# axiom_beta_plugin_module_1xHDMI_in_v0_1_.net
KiCad netlist of a schematic drawn in EAGLE
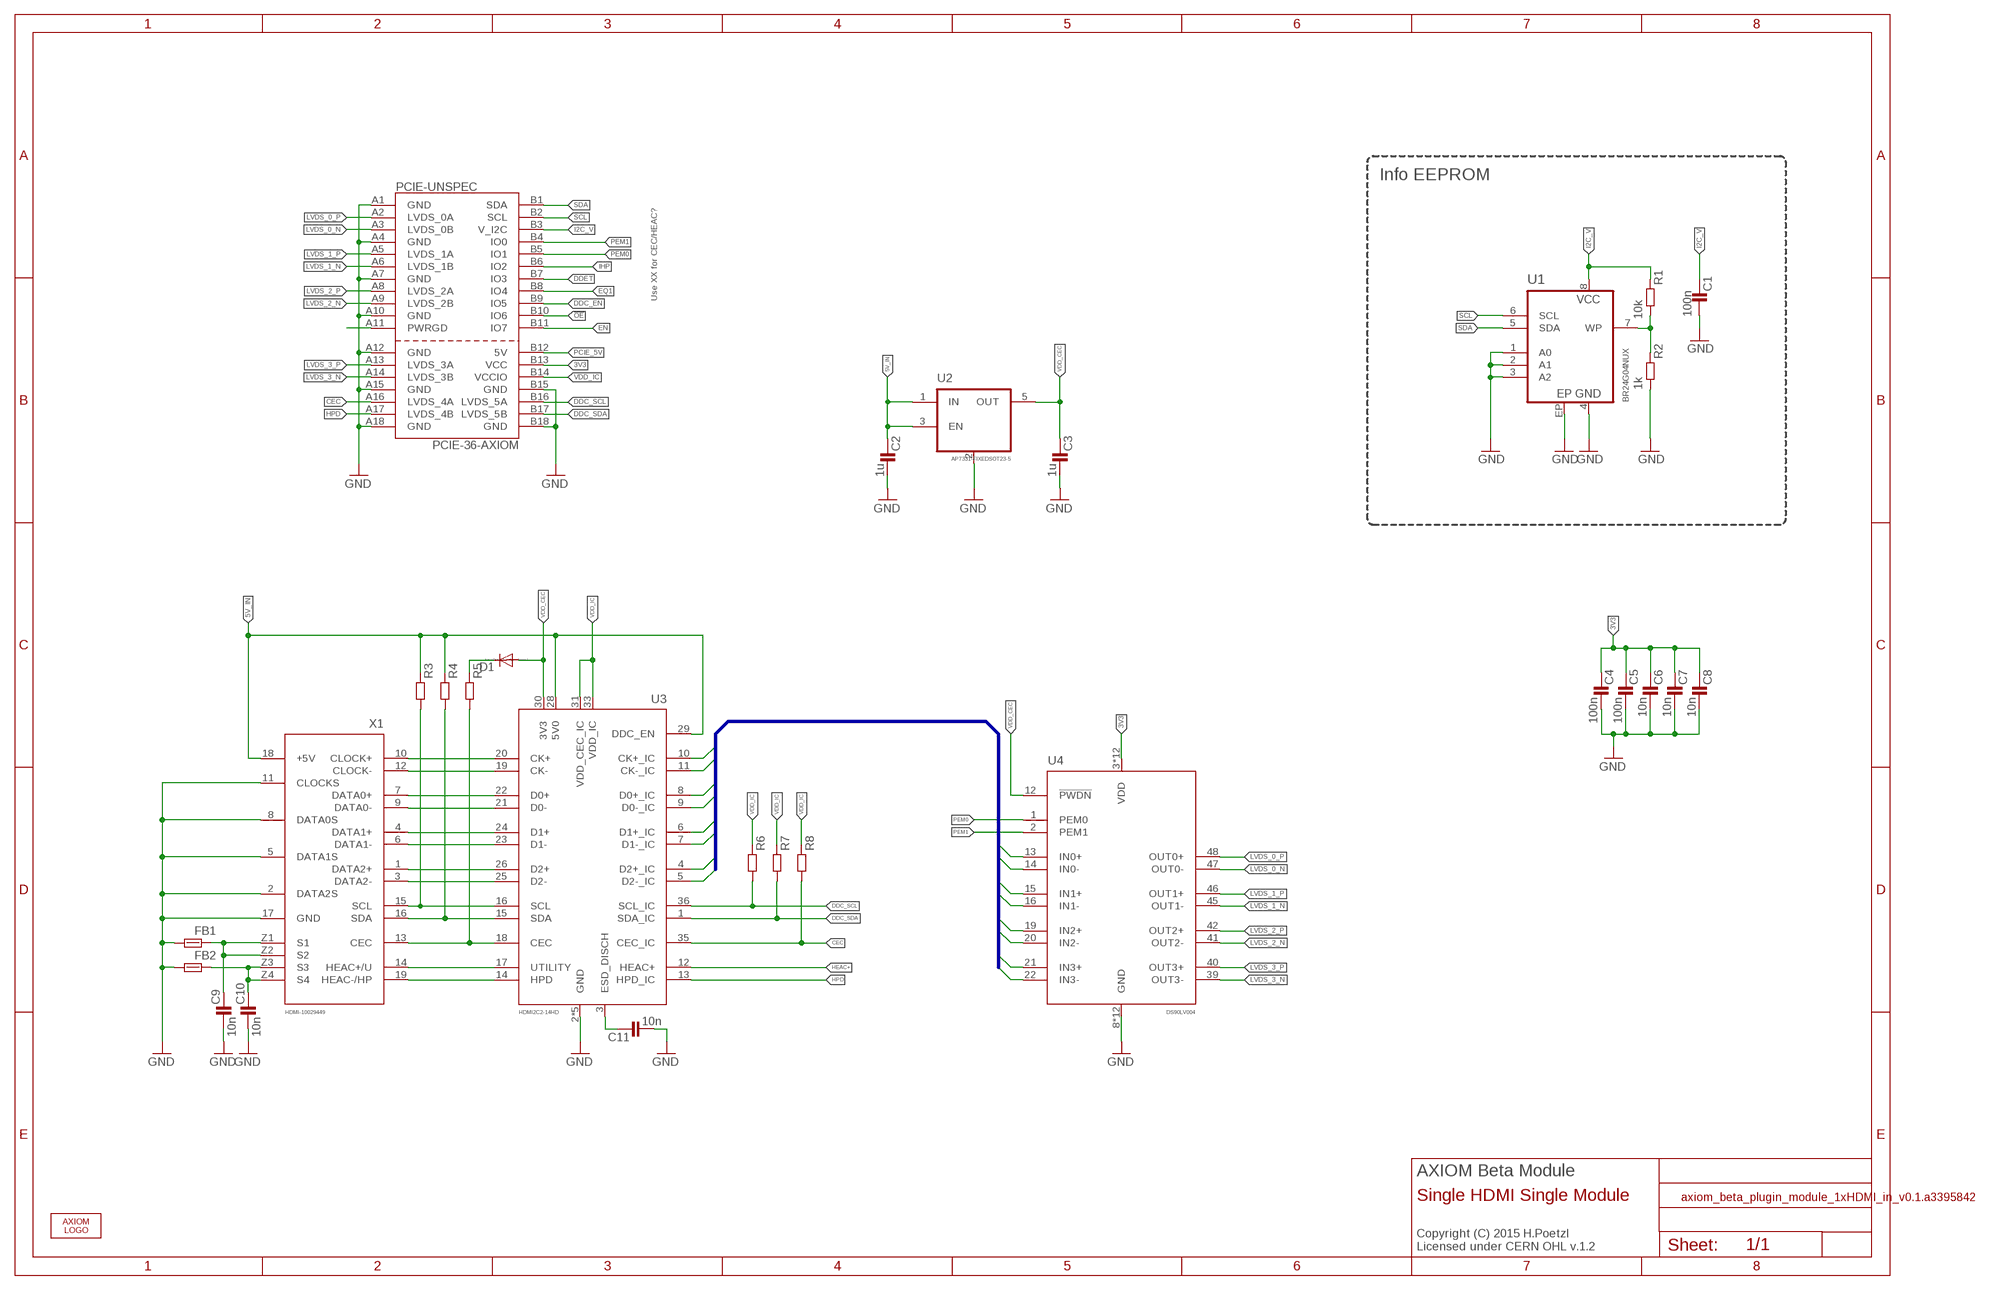
[diagram p0: schematic, sheet 1]

(export (version "E")
  (design (tool "Eeschema 10.0.6"))
  (components
    (comp (ref "C1")
      (value "100n")
      (footprint "eagle-import:0402-B")
      (libsource (lib "eagle-import") (part "C0402-B"))
    )
    (comp (ref "C2")
      (value "1u")
      (footprint "eagle-import:0402-B")
      (libsource (lib "eagle-import") (part "C0402-B"))
    )
    (comp (ref "C3")
      (value "1u")
      (footprint "eagle-import:0402-B")
      (libsource (lib "eagle-import") (part "C0402-B"))
    )
    (comp (ref "C4")
      (value "100n")
      (footprint "eagle-import:0402-B")
      (libsource (lib "eagle-import") (part "C0402-B"))
    )
    (comp (ref "C5")
      (value "100n")
      (footprint "eagle-import:0402-B")
      (libsource (lib "eagle-import") (part "C0402-B"))
    )
    (comp (ref "C6")
      (value "10n")
      (footprint "eagle-import:0402-B")
      (libsource (lib "eagle-import") (part "C0402-B"))
    )
    (comp (ref "C7")
      (value "10n")
      (footprint "eagle-import:0402-B")
      (libsource (lib "eagle-import") (part "C0402-B"))
    )
    (comp (ref "C8")
      (value "10n")
      (footprint "eagle-import:0402-B")
      (libsource (lib "eagle-import") (part "C0402-B"))
    )
    (comp (ref "C9")
      (value "10n")
      (footprint "eagle-import:0402-B")
      (libsource (lib "eagle-import") (part "C0402-B"))
    )
    (comp (ref "C10")
      (value "10n")
      (footprint "eagle-import:0402-B")
      (libsource (lib "eagle-import") (part "C0402-B"))
    )
    (comp (ref "C11")
      (value "10n")
      (footprint "eagle-import:0402-B")
      (libsource (lib "eagle-import") (part "C0402-B"))
    )
    (comp (ref "D1")
      (value "DIODE-SOD523")
      (footprint "eagle-import:SOD523")
      (libsource (lib "eagle-import") (part "DIODE-SOD523"))
    )
    (comp (ref "FB1")
      (value "FB0603-B")
      (footprint "eagle-import:0603-B")
      (libsource (lib "eagle-import") (part "FB0603-B"))
    )
    (comp (ref "FB2")
      (value "FB0603-B")
      (footprint "eagle-import:0603-B")
      (libsource (lib "eagle-import") (part "FB0603-B"))
    )
    (comp (ref "PCIE-UNSPEC")
      (value "PCIE-36-AXIOM")
      (footprint "eagle-import:PCIE-36-AXIOM")
      (libsource (lib "eagle-import") (part "PCIE-36-AXIOM"))
    )
    (comp (ref "R1")
      (value "10k")
      (footprint "eagle-import:0402-B")
      (libsource (lib "eagle-import") (part "R0402-B"))
    )
    (comp (ref "R2")
      (value "1k")
      (footprint "eagle-import:0402-B")
      (libsource (lib "eagle-import") (part "R0402-B"))
    )
    (comp (ref "R3")
      (value "R0402-B")
      (footprint "eagle-import:0402-B")
      (libsource (lib "eagle-import") (part "R0402-B"))
    )
    (comp (ref "R4")
      (value "R0402-B")
      (footprint "eagle-import:0402-B")
      (libsource (lib "eagle-import") (part "R0402-B"))
    )
    (comp (ref "R5")
      (value "R0402-B")
      (footprint "eagle-import:0402-B")
      (libsource (lib "eagle-import") (part "R0402-B"))
    )
    (comp (ref "R6")
      (value "R0402-B")
      (footprint "eagle-import:0402-B")
      (libsource (lib "eagle-import") (part "R0402-B"))
    )
    (comp (ref "R7")
      (value "R0402-B")
      (footprint "eagle-import:0402-B")
      (libsource (lib "eagle-import") (part "R0402-B"))
    )
    (comp (ref "R8")
      (value "R0402-B")
      (footprint "eagle-import:0402-B")
      (libsource (lib "eagle-import") (part "R0402-B"))
    )
    (comp (ref "U$")
      (value "AXIOM_LOGO459X70")
      (footprint "eagle-import:AXIOM_LOGO_459X70")
      (libsource (lib "eagle-import") (part "AXIOM_LOGO459X70"))
    )
    (comp (ref "U1")
      (value "BR24G04NUX")
      (footprint "eagle-import:DFN200X300X100-9N")
      (libsource (lib "eagle-import") (part "BR24G04NUX"))
    )
    (comp (ref "U2")
      (value "AP7331-FIXEDSOT23-5")
      (footprint "eagle-import:SOT23-5")
      (libsource (lib "eagle-import") (part "AP7331-FIXEDSOT23-5"))
    )
    (comp (ref "U3")
      (value "HDMI2C2-14HD")
      (footprint "eagle-import:QFN50P650L90W-25N")
      (libsource (lib "eagle-import") (part "HDMI2C2-14HD"))
    )
    (comp (ref "U4")
      (value "DS90LV004")
      (footprint "eagle-import:QFP50P900X900X160-48N")
      (libsource (lib "eagle-import") (part "DS90LV004"))
    )
    (comp (ref "X1")
      (value "HDMI-10029449")
      (footprint "eagle-import:10029449-X01XLF")
      (libsource (lib "eagle-import") (part "HDMI-10029449"))
    )
  )
  (nets
    (net (code "1") (name "/IN0+") (class "Default")
      (node (ref "U3") (pin "4") (pinfunction "D2+_IC_4") (pintype "bidirectional"))
      (node (ref "U4") (pin "13") (pinfunction "IN0+_13") (pintype "bidirectional"))
    )
    (net (code "2") (name "/IN0-") (class "Default")
      (node (ref "U3") (pin "5") (pinfunction "D2-_IC_5") (pintype "bidirectional"))
      (node (ref "U4") (pin "14") (pinfunction "IN0-_14") (pintype "bidirectional"))
    )
    (net (code "3") (name "/IN1+") (class "Default")
      (node (ref "U3") (pin "6") (pinfunction "D1+_IC_6") (pintype "bidirectional"))
      (node (ref "U4") (pin "15") (pinfunction "IN1+_15") (pintype "bidirectional"))
    )
    (net (code "4") (name "/IN1-") (class "Default")
      (node (ref "U3") (pin "7") (pinfunction "D1-_IC_7") (pintype "bidirectional"))
      (node (ref "U4") (pin "16") (pinfunction "IN1-_16") (pintype "bidirectional"))
    )
    (net (code "5") (name "/IN2+") (class "Default")
      (node (ref "U3") (pin "8") (pinfunction "D0+_IC_8") (pintype "bidirectional"))
      (node (ref "U4") (pin "19") (pinfunction "IN2+_19") (pintype "bidirectional"))
    )
    (net (code "6") (name "/IN2-") (class "Default")
      (node (ref "U3") (pin "9") (pinfunction "D0-_IC_9") (pintype "bidirectional"))
      (node (ref "U4") (pin "20") (pinfunction "IN2-_20") (pintype "bidirectional"))
    )
    (net (code "7") (name "/IN3+") (class "Default")
      (node (ref "U3") (pin "10") (pinfunction "CK+_IC_10") (pintype "bidirectional"))
      (node (ref "U4") (pin "21") (pinfunction "IN3+_21") (pintype "bidirectional"))
    )
    (net (code "8") (name "/IN3-") (class "Default")
      (node (ref "U3") (pin "11") (pinfunction "CK-_IC_11") (pintype "bidirectional"))
      (node (ref "U4") (pin "22") (pinfunction "IN3-_22") (pintype "bidirectional"))
    )
    (net (code "9") (name "/~{OE}") (class "Default")
      (node (ref "PCIE-UNSPEC") (pin "B10") (pinfunction "IO6_B10") (pintype "passive"))
    )
    (net (code "10") (name "3V3") (class "Default")
      (node (ref "C4") (pin "1") (pinfunction "1_1") (pintype "passive"))
      (node (ref "C5") (pin "1") (pinfunction "1_1") (pintype "passive"))
      (node (ref "C6") (pin "1") (pinfunction "1_1") (pintype "passive"))
      (node (ref "C7") (pin "1") (pinfunction "1_1") (pintype "passive"))
      (node (ref "C8") (pin "1") (pinfunction "1_1") (pintype "passive"))
      (node (ref "PCIE-UNSPEC") (pin "B13") (pinfunction "VCC_B13") (pintype "passive"))
      (node (ref "U4") (pin "10") (pinfunction "VDD_10") (pintype "power_in"))
      (node (ref "U4") (pin "11") (pinfunction "VDD_11") (pintype "power_in"))
      (node (ref "U4") (pin "27") (pinfunction "VDD_27") (pintype "power_in"))
      (node (ref "U4") (pin "28") (pinfunction "VDD_28") (pintype "power_in"))
      (node (ref "U4") (pin "29") (pinfunction "VDD_29") (pintype "power_in"))
      (node (ref "U4") (pin "3") (pinfunction "VDD_3") (pintype "power_in"))
      (node (ref "U4") (pin "32") (pinfunction "VDD_32") (pintype "power_in"))
      (node (ref "U4") (pin "33") (pinfunction "VDD_33") (pintype "power_in"))
      (node (ref "U4") (pin "34") (pinfunction "VDD_34") (pintype "power_in"))
      (node (ref "U4") (pin "4") (pinfunction "VDD_4") (pintype "power_in"))
      (node (ref "U4") (pin "5") (pinfunction "VDD_5") (pintype "power_in"))
      (node (ref "U4") (pin "7") (pinfunction "VDD_7") (pintype "power_in"))
    )
    (net (code "11") (name "5V_IN") (class "Default")
      (node (ref "C2") (pin "1") (pinfunction "1_1") (pintype "passive"))
      (node (ref "R3") (pin "1") (pinfunction "1_1") (pintype "passive"))
      (node (ref "R4") (pin "1") (pinfunction "1_1") (pintype "passive"))
      (node (ref "U2") (pin "1") (pinfunction "IN_1") (pintype "power_in"))
      (node (ref "U2") (pin "3") (pinfunction "EN_3") (pintype "input"))
      (node (ref "U3") (pin "28") (pinfunction "5V0_28") (pintype "power_in"))
      (node (ref "U3") (pin "29") (pinfunction "DDC_EN_29") (pintype "bidirectional"))
      (node (ref "X1") (pin "18") (pinfunction "+5V_18") (pintype "power_in"))
    )
    (net (code "12") (name "CEC") (class "Default")
      (node (ref "PCIE-UNSPEC") (pin "A16") (pinfunction "LVDS_4A_A16") (pintype "passive"))
      (node (ref "R8") (pin "2") (pinfunction "2_2") (pintype "passive"))
      (node (ref "U3") (pin "35") (pinfunction "CEC_IC_35") (pintype "bidirectional"))
    )
    (net (code "13") (name "DDC_EN") (class "Default")
      (node (ref "PCIE-UNSPEC") (pin "B9") (pinfunction "IO5_B9") (pintype "passive"))
    )
    (net (code "14") (name "DDC_SCL") (class "Default")
      (node (ref "PCIE-UNSPEC") (pin "B16") (pinfunction "LVDS_5A_B16") (pintype "passive"))
      (node (ref "R6") (pin "2") (pinfunction "2_2") (pintype "passive"))
      (node (ref "U3") (pin "36") (pinfunction "SCL_IC_36") (pintype "bidirectional"))
    )
    (net (code "15") (name "DDC_SDA") (class "Default")
      (node (ref "PCIE-UNSPEC") (pin "B17") (pinfunction "LVDS_5B_B17") (pintype "passive"))
      (node (ref "R7") (pin "2") (pinfunction "2_2") (pintype "passive"))
      (node (ref "U3") (pin "1") (pinfunction "SDA_IC_1") (pintype "bidirectional"))
    )
    (net (code "16") (name "DDET") (class "Default")
      (node (ref "PCIE-UNSPEC") (pin "B7") (pinfunction "IO3_B7") (pintype "passive"))
    )
    (net (code "17") (name "EN") (class "Default")
      (node (ref "PCIE-UNSPEC") (pin "B11") (pinfunction "IO7_B11") (pintype "passive"))
    )
    (net (code "18") (name "EQ1") (class "Default")
      (node (ref "PCIE-UNSPEC") (pin "B8") (pinfunction "IO4_B8") (pintype "passive"))
    )
    (net (code "19") (name "GND") (class "Default")
      (node (ref "C1") (pin "2") (pinfunction "2_2") (pintype "passive"))
      (node (ref "C10") (pin "2") (pinfunction "2_2") (pintype "passive"))
      (node (ref "C11") (pin "2") (pinfunction "2_2") (pintype "passive"))
      (node (ref "C2") (pin "2") (pinfunction "2_2") (pintype "passive"))
      (node (ref "C3") (pin "2") (pinfunction "2_2") (pintype "passive"))
      (node (ref "C4") (pin "2") (pinfunction "2_2") (pintype "passive"))
      (node (ref "C5") (pin "2") (pinfunction "2_2") (pintype "passive"))
      (node (ref "C6") (pin "2") (pinfunction "2_2") (pintype "passive"))
      (node (ref "C7") (pin "2") (pinfunction "2_2") (pintype "passive"))
      (node (ref "C8") (pin "2") (pinfunction "2_2") (pintype "passive"))
      (node (ref "C9") (pin "2") (pinfunction "2_2") (pintype "passive"))
      (node (ref "FB1") (pin "2") (pinfunction "2_2") (pintype "passive"))
      (node (ref "FB2") (pin "2") (pinfunction "2_2") (pintype "passive"))
      (node (ref "PCIE-UNSPEC") (pin "A1") (pinfunction "GND_A1") (pintype "passive"))
      (node (ref "PCIE-UNSPEC") (pin "A10") (pinfunction "GND_A10") (pintype "passive"))
      (node (ref "PCIE-UNSPEC") (pin "A12") (pinfunction "GND_A12") (pintype "passive"))
      (node (ref "PCIE-UNSPEC") (pin "A15") (pinfunction "GND_A15") (pintype "passive"))
      (node (ref "PCIE-UNSPEC") (pin "A18") (pinfunction "GND_A18") (pintype "passive"))
      (node (ref "PCIE-UNSPEC") (pin "A4") (pinfunction "GND_A4") (pintype "passive"))
      (node (ref "PCIE-UNSPEC") (pin "A7") (pinfunction "GND_A7") (pintype "passive"))
      (node (ref "PCIE-UNSPEC") (pin "B15") (pinfunction "GND_B15") (pintype "passive"))
      (node (ref "PCIE-UNSPEC") (pin "B18") (pinfunction "GND_B18") (pintype "passive"))
      (node (ref "R2") (pin "2") (pinfunction "2_2") (pintype "passive"))
      (node (ref "U1") (pin "1") (pinfunction "A0_1") (pintype "input"))
      (node (ref "U1") (pin "2") (pinfunction "A1_2") (pintype "input"))
      (node (ref "U1") (pin "3") (pinfunction "A2_3") (pintype "input"))
      (node (ref "U1") (pin "4") (pinfunction "GND_4") (pintype "passive"))
      (node (ref "U1") (pin "EP") (pinfunction "EP_EP") (pintype "passive"))
      (node (ref "U2") (pin "2") (pinfunction "GND_2") (pintype "power_in"))
      (node (ref "U3") (pin "2") (pinfunction "GND_2") (pintype "power_in"))
      (node (ref "U3") (pin "27") (pinfunction "GND_27") (pintype "power_in"))
      (node (ref "U3") (pin "32") (pinfunction "GND_32") (pintype "power_in"))
      (node (ref "U3") (pin "34") (pinfunction "GND_34") (pintype "power_in"))
      (node (ref "U3") (pin "EP") (pinfunction "GND_EP") (pintype "power_in"))
      (node (ref "U4") (pin "17") (pinfunction "GND_17") (pintype "bidirectional"))
      (node (ref "U4") (pin "18") (pinfunction "GND_18") (pintype "bidirectional"))
      (node (ref "U4") (pin "23") (pinfunction "GND_23") (pintype "bidirectional"))
      (node (ref "U4") (pin "24") (pinfunction "GND_24") (pintype "bidirectional"))
      (node (ref "U4") (pin "25") (pinfunction "GND_25") (pintype "bidirectional"))
      (node (ref "U4") (pin "26") (pinfunction "GND_26") (pintype "bidirectional"))
      (node (ref "U4") (pin "37") (pinfunction "GND_37") (pintype "bidirectional"))
      (node (ref "U4") (pin "38") (pinfunction "GND_38") (pintype "bidirectional"))
      (node (ref "U4") (pin "43") (pinfunction "GND_43") (pintype "bidirectional"))
      (node (ref "U4") (pin "44") (pinfunction "GND_44") (pintype "bidirectional"))
      (node (ref "U4") (pin "8") (pinfunction "GND_8") (pintype "bidirectional"))
      (node (ref "U4") (pin "9") (pinfunction "GND_9") (pintype "bidirectional"))
      (node (ref "X1") (pin "11") (pinfunction "CLOCKS_11") (pintype "power_in"))
      (node (ref "X1") (pin "17") (pinfunction "GND_17") (pintype "bidirectional"))
      (node (ref "X1") (pin "2") (pinfunction "DATA2S_2") (pintype "power_in"))
      (node (ref "X1") (pin "5") (pinfunction "DATA1S_5") (pintype "power_in"))
      (node (ref "X1") (pin "8") (pinfunction "DATA0S_8") (pintype "power_in"))
    )
    (net (code "20") (name "HEAC+") (class "Default")
      (node (ref "U3") (pin "12") (pinfunction "HEAC+_12") (pintype "bidirectional"))
    )
    (net (code "21") (name "HPD") (class "Default")
      (node (ref "PCIE-UNSPEC") (pin "A17") (pinfunction "LVDS_4B_A17") (pintype "passive"))
      (node (ref "U3") (pin "13") (pinfunction "HPD_IC_13") (pintype "bidirectional"))
    )
    (net (code "22") (name "I2C_V") (class "Default")
      (node (ref "C1") (pin "1") (pinfunction "1_1") (pintype "passive"))
      (node (ref "PCIE-UNSPEC") (pin "B3") (pinfunction "V_I2C_B3") (pintype "passive"))
      (node (ref "R1") (pin "1") (pinfunction "1_1") (pintype "passive"))
      (node (ref "U1") (pin "8") (pinfunction "VCC_8") (pintype "power_in"))
    )
    (net (code "23") (name "IHP") (class "Default")
      (node (ref "PCIE-UNSPEC") (pin "B6") (pinfunction "IO2_B6") (pintype "passive"))
    )
    (net (code "24") (name "LVDS_0_N") (class "Default")
      (node (ref "PCIE-UNSPEC") (pin "A3") (pinfunction "LVDS_0B_A3") (pintype "passive"))
      (node (ref "U4") (pin "47") (pinfunction "OUT0-_47") (pintype "bidirectional"))
    )
    (net (code "25") (name "LVDS_0_P") (class "Default")
      (node (ref "PCIE-UNSPEC") (pin "A2") (pinfunction "LVDS_0A_A2") (pintype "passive"))
      (node (ref "U4") (pin "48") (pinfunction "OUT0+_48") (pintype "bidirectional"))
    )
    (net (code "26") (name "LVDS_1_N") (class "Default")
      (node (ref "PCIE-UNSPEC") (pin "A6") (pinfunction "LVDS_1B_A6") (pintype "passive"))
      (node (ref "U4") (pin "45") (pinfunction "OUT1-_45") (pintype "bidirectional"))
    )
    (net (code "27") (name "LVDS_1_P") (class "Default")
      (node (ref "PCIE-UNSPEC") (pin "A5") (pinfunction "LVDS_1A_A5") (pintype "passive"))
      (node (ref "U4") (pin "46") (pinfunction "OUT1+_46") (pintype "bidirectional"))
    )
    (net (code "28") (name "LVDS_2_N") (class "Default")
      (node (ref "PCIE-UNSPEC") (pin "A9") (pinfunction "LVDS_2B_A9") (pintype "passive"))
      (node (ref "U4") (pin "41") (pinfunction "OUT2-_41") (pintype "bidirectional"))
    )
    (net (code "29") (name "LVDS_2_P") (class "Default")
      (node (ref "PCIE-UNSPEC") (pin "A8") (pinfunction "LVDS_2A_A8") (pintype "passive"))
      (node (ref "U4") (pin "42") (pinfunction "OUT2+_42") (pintype "bidirectional"))
    )
    (net (code "30") (name "LVDS_3_N") (class "Default")
      (node (ref "PCIE-UNSPEC") (pin "A14") (pinfunction "LVDS_3B_A14") (pintype "passive"))
      (node (ref "U4") (pin "39") (pinfunction "OUT3-_39") (pintype "bidirectional"))
    )
    (net (code "31") (name "LVDS_3_P") (class "Default")
      (node (ref "PCIE-UNSPEC") (pin "A13") (pinfunction "LVDS_3A_A13") (pintype "passive"))
      (node (ref "U4") (pin "40") (pinfunction "OUT3+_40") (pintype "bidirectional"))
    )
    (net (code "32") (name "Net-(D1-PadC)") (class "Default")
      (node (ref "D1") (pin "C") (pinfunction "C_C") (pintype "passive"))
      (node (ref "R5") (pin "1") (pinfunction "1_1") (pintype "passive"))
    )
    (net (code "33") (name "Net-(U1-WP)") (class "Default")
      (node (ref "R1") (pin "2") (pinfunction "2_2") (pintype "passive"))
      (node (ref "R2") (pin "1") (pinfunction "1_1") (pintype "passive"))
      (node (ref "U1") (pin "7") (pinfunction "WP_7") (pintype "input"))
    )
    (net (code "34") (name "Net-(U3-CEC)") (class "Default")
      (node (ref "R5") (pin "2") (pinfunction "2_2") (pintype "passive"))
      (node (ref "U3") (pin "18") (pinfunction "CEC_18") (pintype "bidirectional"))
      (node (ref "X1") (pin "13") (pinfunction "CEC_13") (pintype "bidirectional"))
    )
    (net (code "35") (name "Net-(U3-CK+)") (class "Default")
      (node (ref "U3") (pin "20") (pinfunction "CK+_20") (pintype "bidirectional"))
      (node (ref "X1") (pin "10") (pinfunction "CLOCK+_10") (pintype "bidirectional"))
    )
    (net (code "36") (name "Net-(U3-CK-)") (class "Default")
      (node (ref "U3") (pin "19") (pinfunction "CK-_19") (pintype "bidirectional"))
      (node (ref "X1") (pin "12") (pinfunction "CLOCK-_12") (pintype "bidirectional"))
    )
    (net (code "37") (name "Net-(U3-D0+)") (class "Default")
      (node (ref "U3") (pin "22") (pinfunction "D0+_22") (pintype "bidirectional"))
      (node (ref "X1") (pin "7") (pinfunction "DATA0+_7") (pintype "bidirectional"))
    )
    (net (code "38") (name "Net-(U3-D0-)") (class "Default")
      (node (ref "U3") (pin "21") (pinfunction "D0-_21") (pintype "bidirectional"))
      (node (ref "X1") (pin "9") (pinfunction "DATA0-_9") (pintype "bidirectional"))
    )
    (net (code "39") (name "Net-(U3-D1+)") (class "Default")
      (node (ref "U3") (pin "24") (pinfunction "D1+_24") (pintype "bidirectional"))
      (node (ref "X1") (pin "4") (pinfunction "DATA1+_4") (pintype "bidirectional"))
    )
    (net (code "40") (name "Net-(U3-D1-)") (class "Default")
      (node (ref "U3") (pin "23") (pinfunction "D1-_23") (pintype "bidirectional"))
      (node (ref "X1") (pin "6") (pinfunction "DATA1-_6") (pintype "bidirectional"))
    )
    (net (code "41") (name "Net-(U3-D2+)") (class "Default")
      (node (ref "U3") (pin "26") (pinfunction "D2+_26") (pintype "bidirectional"))
      (node (ref "X1") (pin "1") (pinfunction "DATA2+_1") (pintype "bidirectional"))
    )
    (net (code "42") (name "Net-(U3-D2-)") (class "Default")
      (node (ref "U3") (pin "25") (pinfunction "D2-_25") (pintype "bidirectional"))
      (node (ref "X1") (pin "3") (pinfunction "DATA2-_3") (pintype "bidirectional"))
    )
    (net (code "43") (name "Net-(U3-ESD_DISCH)") (class "Default")
      (node (ref "C11") (pin "1") (pinfunction "1_1") (pintype "passive"))
      (node (ref "U3") (pin "3") (pinfunction "ESD_DISCH_3") (pintype "power_in"))
    )
    (net (code "44") (name "Net-(U3-HPD)") (class "Default")
      (node (ref "U3") (pin "14") (pinfunction "HPD_14") (pintype "bidirectional"))
      (node (ref "X1") (pin "19") (pinfunction "HEAC-/HP_19") (pintype "bidirectional"))
    )
    (net (code "45") (name "Net-(U3-SCL)") (class "Default")
      (node (ref "R3") (pin "2") (pinfunction "2_2") (pintype "passive"))
      (node (ref "U3") (pin "16") (pinfunction "SCL_16") (pintype "bidirectional"))
      (node (ref "X1") (pin "15") (pinfunction "SCL_15") (pintype "bidirectional"))
    )
    (net (code "46") (name "Net-(U3-SDA)") (class "Default")
      (node (ref "R4") (pin "2") (pinfunction "2_2") (pintype "passive"))
      (node (ref "U3") (pin "15") (pinfunction "SDA_15") (pintype "bidirectional"))
      (node (ref "X1") (pin "16") (pinfunction "SDA_16") (pintype "bidirectional"))
    )
    (net (code "47") (name "Net-(U3-UTILITY)") (class "Default")
      (node (ref "U3") (pin "17") (pinfunction "UTILITY_17") (pintype "bidirectional"))
      (node (ref "X1") (pin "14") (pinfunction "HEAC+/U_14") (pintype "bidirectional"))
    )
    (net (code "48") (name "Net-(X1-S1)") (class "Default")
      (node (ref "C9") (pin "1") (pinfunction "1_1") (pintype "passive"))
      (node (ref "FB1") (pin "1") (pinfunction "1_1") (pintype "passive"))
      (node (ref "X1") (pin "Z1") (pinfunction "S1_Z1") (pintype "power_in"))
      (node (ref "X1") (pin "Z2") (pinfunction "S2_Z2") (pintype "power_in"))
    )
    (net (code "49") (name "Net-(X1-S3)") (class "Default")
      (node (ref "C10") (pin "1") (pinfunction "1_1") (pintype "passive"))
      (node (ref "FB2") (pin "1") (pinfunction "1_1") (pintype "passive"))
      (node (ref "X1") (pin "Z3") (pinfunction "S3_Z3") (pintype "power_in"))
      (node (ref "X1") (pin "Z4") (pinfunction "S4_Z4") (pintype "power_in"))
    )
    (net (code "50") (name "PCIE_5V") (class "Default")
      (node (ref "PCIE-UNSPEC") (pin "B12") (pinfunction "5V_B12") (pintype "passive"))
    )
    (net (code "51") (name "PEM0") (class "Default")
      (node (ref "PCIE-UNSPEC") (pin "B5") (pinfunction "IO1_B5") (pintype "passive"))
      (node (ref "U4") (pin "1") (pinfunction "PEM0_1") (pintype "bidirectional"))
    )
    (net (code "52") (name "PEM1") (class "Default")
      (node (ref "PCIE-UNSPEC") (pin "B4") (pinfunction "IO0_B4") (pintype "passive"))
      (node (ref "U4") (pin "2") (pinfunction "PEM1_2") (pintype "bidirectional"))
    )
    (net (code "53") (name "SCL") (class "Default")
      (node (ref "PCIE-UNSPEC") (pin "B2") (pinfunction "SCL_B2") (pintype "passive"))
      (node (ref "U1") (pin "6") (pinfunction "SCL_6") (pintype "input"))
    )
    (net (code "54") (name "SDA") (class "Default")
      (node (ref "PCIE-UNSPEC") (pin "B1") (pinfunction "SDA_B1") (pintype "passive"))
      (node (ref "U1") (pin "5") (pinfunction "SDA_5") (pintype "bidirectional"))
    )
    (net (code "55") (name "VDD_CEC") (class "Default")
      (node (ref "C3") (pin "1") (pinfunction "1_1") (pintype "passive"))
      (node (ref "D1") (pin "A") (pinfunction "A_A") (pintype "passive"))
      (node (ref "U2") (pin "5") (pinfunction "OUT_5") (pintype "power_in"))
      (node (ref "U3") (pin "30") (pinfunction "3V3_30") (pintype "power_in"))
      (node (ref "U4") (pin "12") (pinfunction "~{PWDN}_12") (pintype "bidirectional"))
    )
    (net (code "56") (name "VDD_IC") (class "Default")
      (node (ref "PCIE-UNSPEC") (pin "B14") (pinfunction "VCCIO_B14") (pintype "passive"))
      (node (ref "R6") (pin "1") (pinfunction "1_1") (pintype "passive"))
      (node (ref "R7") (pin "1") (pinfunction "1_1") (pintype "passive"))
      (node (ref "R8") (pin "1") (pinfunction "1_1") (pintype "passive"))
      (node (ref "U3") (pin "31") (pinfunction "VDD_CEC_IC_31") (pintype "power_in"))
      (node (ref "U3") (pin "33") (pinfunction "VDD_IC_33") (pintype "power_in"))
    )
    (net (code "57") (name "unconnected-(PCIE-UNSPEC-PWRGD-PadA11)") (class "Default")
      (node (ref "PCIE-UNSPEC") (pin "A11") (pinfunction "PWRGD_A11") (pintype "passive"))
    )
  )
)
